# CAN.net
KiCad netlist of a schematic drawn in Altium Designer
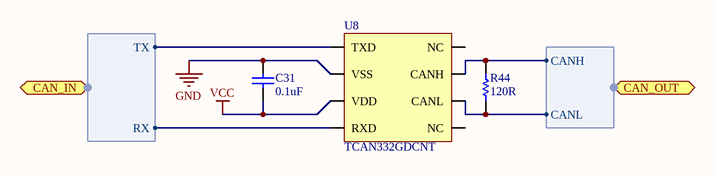
[diagram p0: CAN.SchDoc]

(export (version "E")
  (design (tool "Eeschema 10.0.6"))
  (components
    (comp (ref "C31")
      (value "0.1uF")
      (footprint "C0402[1005X55]")
      (description "0.1uF 6.3V 10% 0402 (1005 Metric)")
      (fields (field (name "TOLERANCE") "10%") (field (name "PARTNUMBER") "GRM155R70J104KA01D"))
      (libsource (lib "Capacitors") (part "CAP_0.1uF_6.3V_0402_10%"))
    )
    (comp (ref "R44")
      (value "120R")
      (footprint "R0402[1005]")
      (description "120R 0.063W 1% 0402 (1005 Metric)")
      (fields (field (name "TOLERANCE") "1%") (field (name "POWER") "0.063W"))
      (libsource (lib "Resistors") (part "RES_120R_0402_1%"))
    )
    (comp (ref "U8")
      (value "TCAN332GDCNT")
      (footprint "SOT-23-8")
      (description "CAN Interface IC 3.3-V CAN Transceivers with CAN FD (Flexible Data Rate) 8-SOT-23 -40 to 125")
      (fields (field (name "MANUFACTURER") "Texas Instruments"))
      (libsource (lib "ICs-CANTransceivers") (part "TCAN332GDCNT"))
    )
  )
  (nets
    (net (code "4") (name "/CANH") (class "Default")
      (node (ref "R44") (pin "2") (pinfunction "2_2") (pintype "passive"))
      (node (ref "U8") (pin "7") (pinfunction "CANH_7") (pintype "passive"))
    )
    (net (code "5") (name "/CANL") (class "Default")
      (node (ref "R44") (pin "1") (pinfunction "1_1") (pintype "passive"))
      (node (ref "U8") (pin "6") (pinfunction "CANL_6") (pintype "passive"))
    )
    (net (code "6") (name "/RX") (class "Default")
      (node (ref "U8") (pin "4") (pinfunction "RXD_4") (pintype "passive"))
    )
    (net (code "7") (name "/TX") (class "Default")
      (node (ref "U8") (pin "1") (pinfunction "TXD_1") (pintype "passive"))
    )
    (net (code "10") (name "GND") (class "Default")
      (node (ref "C31") (pin "1") (pinfunction "1_1") (pintype "passive"))
      (node (ref "U8") (pin "2") (pinfunction "VSS_2") (pintype "passive"))
    )
    (net (code "11") (name "VCC") (class "Default")
      (node (ref "C31") (pin "2") (pinfunction "2_2") (pintype "passive"))
      (node (ref "U8") (pin "3") (pinfunction "VDD_3") (pintype "passive"))
    )
    (net (code "12") (name "unconnected-(U8-NC-Pad5)") (class "Default")
      (node (ref "U8") (pin "5") (pinfunction "NC_5") (pintype "passive"))
    )
    (net (code "13") (name "unconnected-(U8-NC-Pad8)") (class "Default")
      (node (ref "U8") (pin "8") (pinfunction "NC_8") (pintype "passive"))
    )
  )
)
